# PCB2.net
KiCad netlist of a schematic drawn in Altium Designer
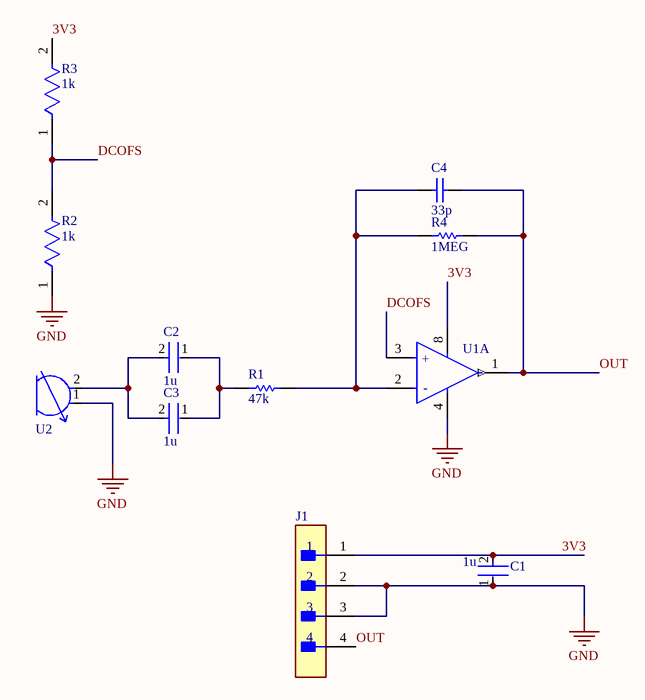
[diagram p0: PCB2.SchDoc]

(export (version "E")
  (design (tool "Eeschema 10.0.6"))
  (components
    (comp (ref "C1")
      (value "1u")
      (footprint "FP-GRM31C-0_3-e0_3_0_9-IPC_C")
      (description "Chip Multilayer Ceramic Capacitors for General Purpose, 1206, 220uF, X5R, 15%, 20%, 4V")
      (fields (field (name "TOLERANCE") "20%"))
      (libsource (lib "Altium Content Vault") (part "f23184f103b6ebe33a8c269c53dcba6"))
    )
    (comp (ref "C2")
      (value "1u")
      (footprint "FP-GRM31C-0_3-e0_3_0_9-IPC_C")
      (description "Chip Multilayer Ceramic Capacitors for General Purpose, 1206, 220uF, X5R, 15%, 20%, 4V")
      (fields (field (name "TOLERANCE") "20%"))
      (libsource (lib "Altium Content Vault") (part "f23184f103b6ebe33a8c269c53dcba6"))
    )
    (comp (ref "C3")
      (value "1u")
      (footprint "FP-GRM31C-0_3-e0_3_0_9-IPC_C")
      (description "Chip Multilayer Ceramic Capacitors for General Purpose, 1206, 220uF, X5R, 15%, 20%, 4V")
      (fields (field (name "TOLERANCE") "20%"))
      (libsource (lib "Altium Content Vault") (part "f23184f103b6ebe33a8c269c53dcba6"))
    )
    (comp (ref "C4")
      (value "33p")
      (footprint "CAPC1206(3216)170_L")
      (description "CAP 33pF 100V ±2% 1206 (3216 Metric) Thickness 1.7mm SMD")
      (fields (field (name "TOLERANCE") "Â±2%"))
      (libsource (lib "Altium Content Vault") (part "CAP"))
    )
    (comp (ref "J1")
      (value "HDR")
      (footprint "FP-MTLW-104-05-G-S-185-MFG")
      (description "CONN HEADER VERT 4POS 2.54MM")
      (libsource (lib "Altium Content Vault") (part "299a8cea1bdcbc3624fe62c390fa72c"))
    )
    (comp (ref "R1")
      (value "47k")
      (footprint "RESC3216X70X50LL05T20")
      (fields (field (name "PART NUMBER") "ERJ-8GEYJ473V") (field (name "MANUFACTURER") "Panasonic"))
      (libsource (lib "Altium Content Vault") (part "RES"))
    )
    (comp (ref "R2")
      (value "1k")
      (footprint "FP-RMCF1206-MFG")
      (description "1kΩ ±5% 0.25W 1206 Thick Film Chip Resistor AEC-Q200 compliant")
      (fields (field (name "TOLERANCE") "5%"))
      (libsource (lib "Altium Content Vault") (part "1029c3af85768c4190bb7ad29bc67b5"))
    )
    (comp (ref "R3")
      (value "1k")
      (footprint "FP-RMCF1206-MFG")
      (description "1kΩ ±5% 0.25W 1206 Thick Film Chip Resistor AEC-Q200 compliant")
      (fields (field (name "TOLERANCE") "5%"))
      (libsource (lib "Altium Content Vault") (part "1029c3af85768c4190bb7ad29bc67b5"))
    )
    (comp (ref "R4")
      (value "1MEG")
      (footprint "RESC3216X70X40LL20T20")
      (fields (field (name "MANUFACTURER") "KOA Speer") (field (name "PART NUMBER") "RK73B2BTTD105J"))
      (libsource (lib "Altium Content Vault") (part "RES"))
    )
    (comp (ref "U1")
      (value "LM358DR2G")
      (footprint "FP-751-07-IPC_C")
      (description "IC OPAMP GP 2 CIRCUIT 8SOIC")
      (libsource (lib "Altium Content Vault") (part "992a6607d1d88c80ee6b45e5ba6cb1b"))
    )
    (comp (ref "U2")
      (value "POM-3535P-3-R")
      (footprint "FP-POM-3535P-3-R-MFG")
      (description "MIC COND ANALOG OMNI -35DB 6MM D")
      (libsource (lib "Altium Content Vault") (part "8932b53fa08aabe3022b5f676529f57"))
    )
  )
  (nets
    (net (code "1") (name "/3V3") (class "Default")
      (node (ref "C1") (pin "2") (pinfunction "2_2") (pintype "passive"))
      (node (ref "J1") (pin "1") (pinfunction "1_1") (pintype "passive"))
      (node (ref "R3") (pin "2") (pinfunction "2_2") (pintype "passive"))
      (node (ref "U1") (pin "8") (pinfunction "VCC_8") (pintype "power_in"))
    )
    (net (code "2") (name "/DCOFS") (class "Default")
      (node (ref "R2") (pin "2") (pinfunction "2_2") (pintype "passive"))
      (node (ref "R3") (pin "1") (pinfunction "1_1") (pintype "passive"))
      (node (ref "U1") (pin "3") (pinfunction "INPUT_A+_3") (pintype "tri_state"))
    )
    (net (code "3") (name "/OUT") (class "Default")
      (node (ref "C4") (pin "2") (pinfunction "2_2") (pintype "passive"))
      (node (ref "J1") (pin "4") (pinfunction "4_4") (pintype "passive"))
      (node (ref "R4") (pin "2") (pinfunction "2_2") (pintype "passive"))
      (node (ref "U1") (pin "1") (pinfunction "OUTPUT_A_1") (pintype "output"))
    )
    (net (code "4") (name "GND") (class "Default")
      (node (ref "C1") (pin "1") (pinfunction "1_1") (pintype "passive"))
      (node (ref "J1") (pin "2") (pinfunction "2_2") (pintype "passive"))
      (node (ref "J1") (pin "3") (pinfunction "3_3") (pintype "passive"))
      (node (ref "R2") (pin "1") (pinfunction "1_1") (pintype "passive"))
      (node (ref "U1") (pin "4") (pinfunction "VEE/GND_4") (pintype "power_in"))
      (node (ref "U2") (pin "1") (pinfunction "A_1") (pintype "passive"))
    )
    (net (code "5") (name "Net-(C2-Pad1)") (class "Default")
      (node (ref "C2") (pin "1") (pinfunction "1_1") (pintype "passive"))
      (node (ref "C3") (pin "1") (pinfunction "1_1") (pintype "passive"))
      (node (ref "R1") (pin "1") (pinfunction "1_1") (pintype "passive"))
    )
    (net (code "6") (name "Net-(U1A-INPUT_A-)") (class "Default")
      (node (ref "C4") (pin "1") (pinfunction "1_1") (pintype "passive"))
      (node (ref "R1") (pin "2") (pinfunction "2_2") (pintype "passive"))
      (node (ref "R4") (pin "1") (pinfunction "1_1") (pintype "passive"))
      (node (ref "U1") (pin "2") (pinfunction "INPUT_A-_2") (pintype "tri_state"))
    )
    (net (code "7") (name "Net-(U2-C)") (class "Default")
      (node (ref "C2") (pin "2") (pinfunction "2_2") (pintype "passive"))
      (node (ref "C3") (pin "2") (pinfunction "2_2") (pintype "passive"))
      (node (ref "U2") (pin "2") (pinfunction "C_2") (pintype "passive"))
    )
  )
)
